# bridge.net
KiCad netlist of a schematic drawn in Altium Designer
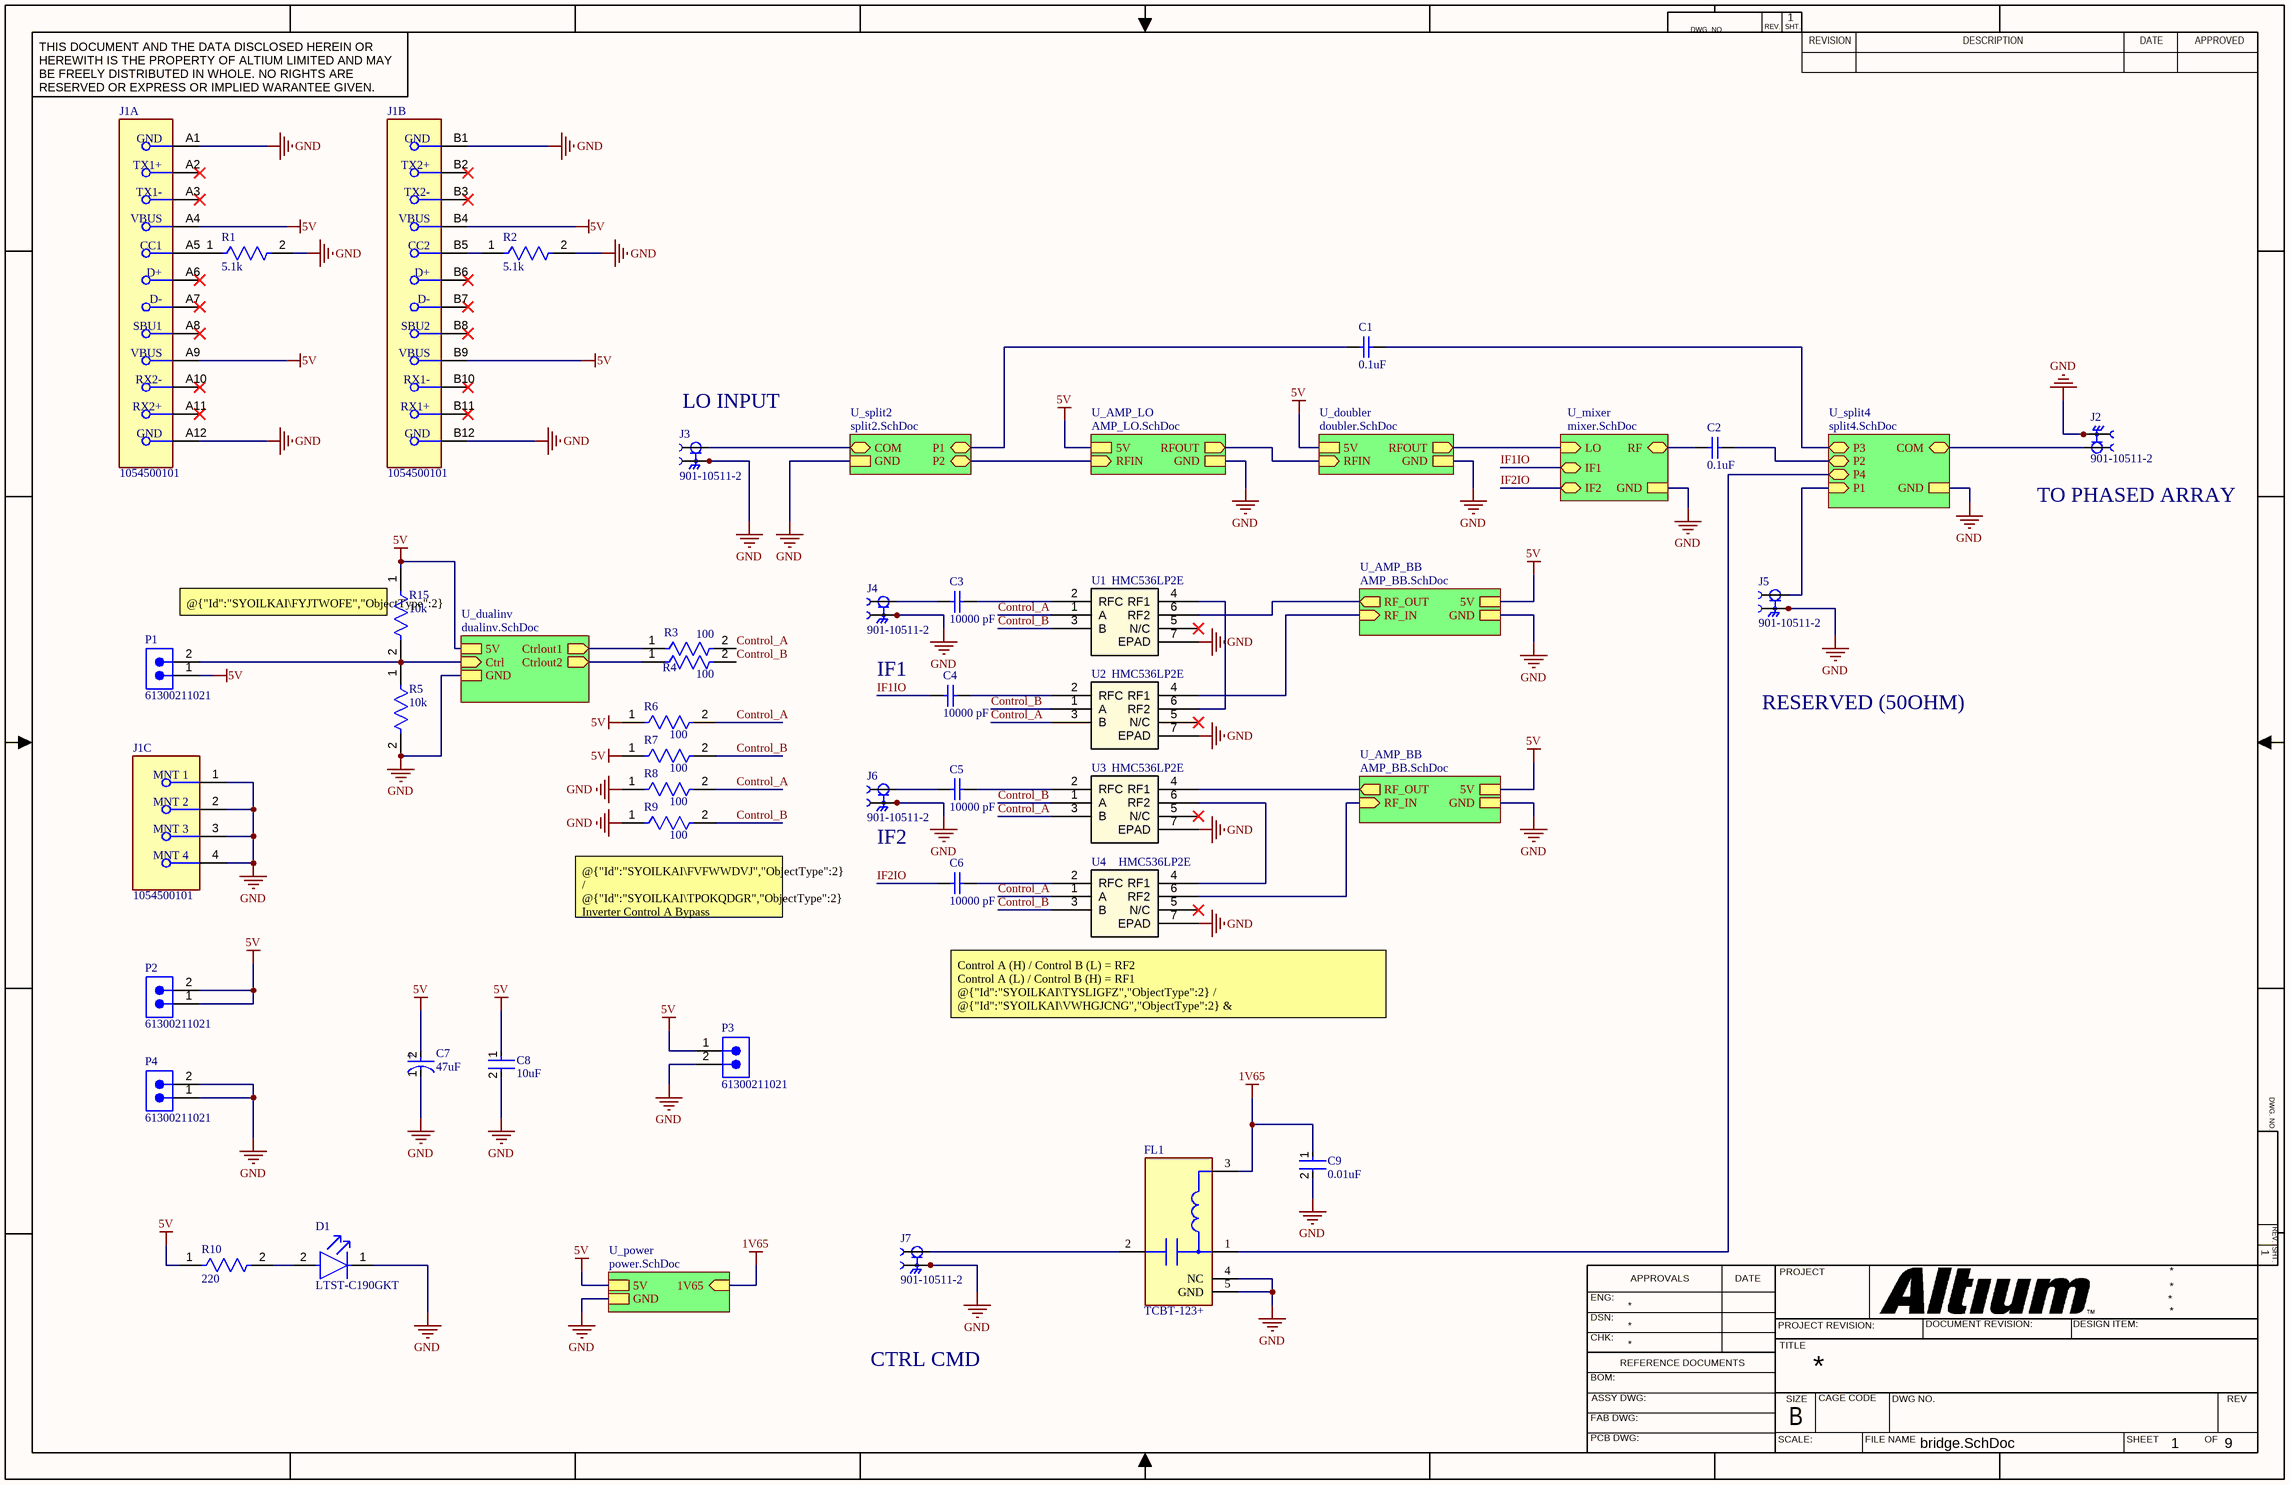
[diagram p0: bridge.SchDoc]

(export (version "E")
  (design (tool "Eeschema 10.0.6"))
  (components
    (comp (ref "C1")
      (value "0.1uF")
      (footprint "CAPC0603X33X15LL03T05")
      (description "CAP CER 0.1UF 16V X5R 0201, Broadband\r\nMultilayer Capacitor")
      (fields (field (name "MANUFACTURER") "KYOCERA AVX") (field (name "PART NUMBER") "531Z104KT16T"))
      (libsource (lib "FullLib") (part "CMP-2010-00245-1"))
    )
    (comp (ref "C2")
      (value "0.1uF")
      (footprint "CAPC0603X33X15LL03T05")
      (description "CAP CER 0.1UF 16V X5R 0201, Broadband\r\nMultilayer Capacitor")
      (fields (field (name "MANUFACTURER") "KYOCERA AVX") (field (name "PART NUMBER") "531Z104KT16T"))
      (libsource (lib "FullLib") (part "CMP-2010-00245-1"))
    )
    (comp (ref "C3")
      (value "10000 pF")
      (footprint "CAPC1005X55X25ML05T10")
      (description "CAP CER 10000PF 16V X7R 0402, RF Series")
      (fields (field (name "MANUFACTURER") "KYOCERA AVX") (field (name "PART NUMBER") "520L103KT16T"))
      (libsource (lib "FullLib") (part "CNP-CAP-10000PF-RF"))
    )
    (comp (ref "C4")
      (value "10000 pF")
      (footprint "CAPC1005X55X25ML05T10")
      (description "CAP CER 10000PF 16V X7R 0402, RF Series")
      (fields (field (name "MANUFACTURER") "KYOCERA AVX") (field (name "PART NUMBER") "520L103KT16T"))
      (libsource (lib "FullLib") (part "CNP-CAP-10000PF-RF"))
    )
    (comp (ref "C5")
      (value "10000 pF")
      (footprint "CAPC1005X55X25ML05T10")
      (description "CAP CER 10000PF 16V X7R 0402, RF Series")
      (fields (field (name "MANUFACTURER") "KYOCERA AVX") (field (name "PART NUMBER") "520L103KT16T"))
      (libsource (lib "FullLib") (part "CNP-CAP-10000PF-RF"))
    )
    (comp (ref "C6")
      (value "10000 pF")
      (footprint "CAPC1005X55X25ML05T10")
      (description "CAP CER 10000PF 16V X7R 0402, RF Series")
      (fields (field (name "MANUFACTURER") "KYOCERA AVX") (field (name "PART NUMBER") "520L103KT16T"))
      (libsource (lib "FullLib") (part "CNP-CAP-10000PF-RF"))
    )
    (comp (ref "C7")
      (value "47uF")
      (footprint "FP-TAJB-MFG")
      (description "47uF 10V  ±10% 1Ω 1210  SMD Tantalum Capacitor")
      (fields (field (name "VOLTAGE") "10V") (field (name "TOLERANCE") "10%"))
      (libsource (lib "FullLib") (part "CMP-04424-000629-1"))
    )
    (comp (ref "C8")
      (value "10uF")
      (footprint "FP-ZRB18AR61E106ME01L-MFG")
      (description "CAP CER 10UF 25V X5R 0603")
      (fields (field (name "VOLTAGE") "25V") (field (name "TOLERANCE") "20%"))
      (libsource (lib "FullLib") (part "CMP-06035-062385-2"))
    )
    (comp (ref "C9")
      (value "0.01uF")
      (footprint "FP-C0402-BB-MFG")
      (description "CAP CER 10000PF 50V X7R 0402")
      (fields (field (name "TOLERANCE") "0.1") (field (name "MANUFACTURER") "Murata"))
      (libsource (lib "FullLib") (part "CMP-2008-02109-2"))
    )
    (comp (ref "D1")
      (value "LTST-C190GKT")
      (footprint "FP-LTST-C190GKT-MFG")
      (description "LED GREEN CLEAR CHIP SMD")
      (fields (field (name "VOLTAGE") "2V") (field (name "MANUFACTURER") "Lite-On"))
      (libsource (lib "FullLib") (part "CMP-22017-000005-2"))
    )
    (comp (ref "FL1")
      (value "TCBT-123+")
      (footprint "FP-GU1414-MFG")
      (description "TCBT-123+ OEMs, CMs ONLY (NO BROKERS),  \r\nBIAS TEE SMT, 10 MHZ - 12 GHZ, 5")
      (fields (field (name "MANUFACTURER") "Mini-Circuits"))
      (libsource (lib "FullLib") (part "CMP-01968-107855816-1"))
    )
    (comp (ref "J1")
      (value "1054500101")
      (footprint "FP-1054500101-MFG")
      (description "CONN RCP USB3.1 TYPEC 24P SMD RA")
      (fields (field (name "MANUFACTURER") "Molex"))
      (libsource (lib "FullLib") (part "CMP-04767-000004-1"))
    )
    (comp (ref "J2")
      (value "901-10511-2")
      (footprint "AMPHENOL_901-10511-2")
      (fields (field (name "MANUFACTURER") "Amphenol RF"))
      (libsource (lib "Connectors") (part "901-10511-2"))
    )
    (comp (ref "J3")
      (value "901-10511-2")
      (footprint "AMPHENOL_901-10511-2")
      (fields (field (name "MANUFACTURER") "Amphenol RF"))
      (libsource (lib "Connectors") (part "901-10511-2"))
    )
    (comp (ref "J4")
      (value "901-10511-2")
      (footprint "AMPHENOL_901-10511-2")
      (fields (field (name "MANUFACTURER") "Amphenol RF"))
      (libsource (lib "Connectors") (part "901-10511-2"))
    )
    (comp (ref "J5")
      (value "901-10511-2")
      (footprint "AMPHENOL_901-10511-2")
      (fields (field (name "MANUFACTURER") "Amphenol RF"))
      (libsource (lib "Connectors") (part "901-10511-2"))
    )
    (comp (ref "J6")
      (value "901-10511-2")
      (footprint "AMPHENOL_901-10511-2")
      (fields (field (name "MANUFACTURER") "Amphenol RF"))
      (libsource (lib "Connectors") (part "901-10511-2"))
    )
    (comp (ref "J7")
      (value "901-10511-2")
      (footprint "AMPHENOL_901-10511-2")
      (fields (field (name "MANUFACTURER") "Amphenol RF"))
      (libsource (lib "Connectors") (part "901-10511-2"))
    )
    (comp (ref "P1")
      (value "61300211021")
      (footprint "61300211021")
      (description "CONN HEADER R/A 2POS 2.54MM")
      (fields (field (name "MANUFACTURER") "Wurth"))
      (libsource (lib "FullLib") (part "CMP-1502-01059-3"))
    )
    (comp (ref "P2")
      (value "61300211021")
      (footprint "61300211021")
      (description "CONN HEADER R/A 2POS 2.54MM")
      (fields (field (name "MANUFACTURER") "Wurth"))
      (libsource (lib "FullLib") (part "CMP-1502-01059-3"))
    )
    (comp (ref "P3")
      (value "61300211021")
      (footprint "61300211021")
      (description "CONN HEADER R/A 2POS 2.54MM")
      (fields (field (name "MANUFACTURER") "Wurth"))
      (libsource (lib "FullLib") (part "CMP-1502-01059-3"))
    )
    (comp (ref "P4")
      (value "61300211021")
      (footprint "61300211021")
      (description "CONN HEADER R/A 2POS 2.54MM")
      (fields (field (name "MANUFACTURER") "Wurth"))
      (libsource (lib "FullLib") (part "CMP-1502-01059-3"))
    )
    (comp (ref "R1")
      (value "5.1k")
      (footprint "FP-CRCW0603-e3-IPC_C")
      (description "RES Thick Film, 5.1kΩ, 1%, 0.1W, 100ppm/°C, 0603")
      (fields (field (name "TOLERANCE") "1%") (field (name "PART NUMBER") "ERJ-3EKF5101V"))
      (libsource (lib "FullLib") (part "CMP-1012-00590-3"))
    )
    (comp (ref "R2")
      (value "5.1k")
      (footprint "FP-CRCW0603-e3-IPC_C")
      (description "RES Thick Film, 5.1kΩ, 1%, 0.1W, 100ppm/°C, 0603")
      (fields (field (name "TOLERANCE") "1%") (field (name "PART NUMBER") "ERJ-3EKF5101V"))
      (libsource (lib "FullLib") (part "CMP-1012-00590-3"))
    )
    (comp (ref "R3")
      (value "100")
      (footprint "FP-RC0603-0_55-MFG")
      (description "RES SMD 100 OHM 5% 1/10W 0603")
      (fields (field (name "TOLERANCE") "5%") (field (name "MANUFACTURER") "Panasonic"))
      (libsource (lib "FullLib") (part "CMP-2000-05021-2"))
    )
    (comp (ref "R4")
      (value "100")
      (footprint "FP-RC0603-0_55-MFG")
      (description "RES SMD 100 OHM 5% 1/10W 0603")
      (fields (field (name "TOLERANCE") "5%") (field (name "MANUFACTURER") "Panasonic"))
      (libsource (lib "FullLib") (part "CMP-2000-05021-2"))
    )
    (comp (ref "R5")
      (value "10k")
      (footprint "FP-RC0603-0_55-IPC_C")
      (description "RES 10K OHM 1% 1/10W 0603")
      (fields (field (name "TOLERANCE") "1%") (field (name "PART NUMBER") "ERJ-S03F1002V"))
      (libsource (lib "FullLib") (part "CMP-2100-03664-2"))
    )
    (comp (ref "R6")
      (value "100")
      (footprint "FP-RC0603-0_55-MFG")
      (description "RES SMD 100 OHM 5% 1/10W 0603")
      (fields (field (name "TOLERANCE") "5%") (field (name "MANUFACTURER") "Panasonic"))
      (libsource (lib "FullLib") (part "CMP-2000-05021-2"))
    )
    (comp (ref "R7")
      (value "100")
      (footprint "FP-RC0603-0_55-MFG")
      (description "RES SMD 100 OHM 5% 1/10W 0603")
      (fields (field (name "TOLERANCE") "5%") (field (name "MANUFACTURER") "Panasonic"))
      (libsource (lib "FullLib") (part "CMP-2000-05021-2"))
    )
    (comp (ref "R8")
      (value "100")
      (footprint "FP-RC0603-0_55-MFG")
      (description "RES SMD 100 OHM 5% 1/10W 0603")
      (fields (field (name "TOLERANCE") "5%") (field (name "MANUFACTURER") "Panasonic"))
      (libsource (lib "FullLib") (part "CMP-2000-05021-2"))
    )
    (comp (ref "R9")
      (value "100")
      (footprint "FP-RC0603-0_55-MFG")
      (description "RES SMD 100 OHM 5% 1/10W 0603")
      (fields (field (name "TOLERANCE") "5%") (field (name "MANUFACTURER") "Panasonic"))
      (libsource (lib "FullLib") (part "CMP-2000-05021-2"))
    )
    (comp (ref "R10")
      (value "220")
      (footprint "FP-ERJ3G-MFG")
      (description "RES SMD 220 OHM 5% 1/10W 0603")
      (fields (field (name "TOLERANCE") "5%") (field (name "MANUFACTURER") "Panasonic"))
      (libsource (lib "FullLib") (part "CMP-2000-00746-2"))
    )
    (comp (ref "R15")
      (value "10k")
      (footprint "FP-RC0603-0_55-IPC_C")
      (description "RES 10K OHM 1% 1/10W 0603")
      (fields (field (name "TOLERANCE") "1%") (field (name "PART NUMBER") "ERJ-S03F1002V"))
      (libsource (lib "FullLib") (part "CMP-2100-03664-2"))
    )
    (comp (ref "U1")
      (value "HMC536LP2E")
      (footprint "HMC536LP2E")
      (description "IC RF SWITCH SPDT 6GHZ 6DFN")
      (fields (field (name "MANUFACTURER") "Analog Devices"))
      (libsource (lib "FullyDigital") (part "HMC536LP2E"))
    )
    (comp (ref "U2")
      (value "HMC536LP2E")
      (footprint "HMC536LP2E")
      (description "IC RF SWITCH SPDT 6GHZ 6DFN")
      (fields (field (name "MANUFACTURER") "Analog Devices"))
      (libsource (lib "FullyDigital") (part "HMC536LP2E"))
    )
    (comp (ref "U3")
      (value "HMC536LP2E")
      (footprint "HMC536LP2E")
      (description "IC RF SWITCH SPDT 6GHZ 6DFN")
      (fields (field (name "MANUFACTURER") "Analog Devices"))
      (libsource (lib "FullyDigital") (part "HMC536LP2E"))
    )
    (comp (ref "U4")
      (value "HMC536LP2E")
      (footprint "HMC536LP2E")
      (description "IC RF SWITCH SPDT 6GHZ 6DFN")
      (fields (field (name "MANUFACTURER") "Analog Devices"))
      (libsource (lib "FullyDigital") (part "HMC536LP2E"))
    )
  )
  (nets
    (net (code "1") (name "/COM") (class "Default")
      (node (ref "J2") (pin "1") (pinfunction "1_1") (pintype "passive"))
    )
    (net (code "2") (name "/COM_1") (class "Default")
      (node (ref "J3") (pin "1") (pinfunction "1_1") (pintype "passive"))
    )
    (net (code "3") (name "/Control_A") (class "Default")
      (node (ref "R3") (pin "2") (pinfunction "2_2") (pintype "passive"))
      (node (ref "R6") (pin "2") (pinfunction "2_2") (pintype "passive"))
      (node (ref "R8") (pin "2") (pinfunction "2_2") (pintype "passive"))
      (node (ref "U1") (pin "1") (pinfunction "A_1") (pintype "passive"))
      (node (ref "U2") (pin "3") (pinfunction "B_3") (pintype "passive"))
      (node (ref "U3") (pin "3") (pinfunction "B_3") (pintype "passive"))
      (node (ref "U4") (pin "1") (pinfunction "A_1") (pintype "passive"))
    )
    (net (code "4") (name "/Control_B") (class "Default")
      (node (ref "R4") (pin "2") (pinfunction "2_2") (pintype "passive"))
      (node (ref "R7") (pin "2") (pinfunction "2_2") (pintype "passive"))
      (node (ref "R9") (pin "2") (pinfunction "2_2") (pintype "passive"))
      (node (ref "U1") (pin "3") (pinfunction "B_3") (pintype "passive"))
      (node (ref "U2") (pin "1") (pinfunction "A_1") (pintype "passive"))
      (node (ref "U3") (pin "1") (pinfunction "A_1") (pintype "passive"))
      (node (ref "U4") (pin "3") (pinfunction "B_3") (pintype "passive"))
    )
    (net (code "5") (name "/Ctrl") (class "Default")
      (node (ref "P1") (pin "2") (pinfunction "2_2") (pintype "passive"))
      (node (ref "R15") (pin "2") (pinfunction "2_2") (pintype "passive"))
      (node (ref "R5") (pin "1") (pinfunction "1_1") (pintype "passive"))
    )
    (net (code "6") (name "/Ctrlout1") (class "Default")
      (node (ref "R3") (pin "1") (pinfunction "1_1") (pintype "passive"))
    )
    (net (code "7") (name "/Ctrlout2") (class "Default")
      (node (ref "R4") (pin "1") (pinfunction "1_1") (pintype "passive"))
    )
    (net (code "8") (name "/IF1IO") (class "Default")
      (node (ref "C4") (pin "1") (pinfunction "1_1") (pintype "passive"))
    )
    (net (code "9") (name "/IF2IO") (class "Default")
      (node (ref "C6") (pin "1") (pinfunction "1_1") (pintype "passive"))
    )
    (net (code "10") (name "/P1") (class "Default")
      (node (ref "J5") (pin "1") (pinfunction "1_1") (pintype "passive"))
    )
    (net (code "11") (name "/P1_1") (class "Default")
      (node (ref "C1") (pin "1") (pinfunction "1_1") (pintype "passive"))
    )
    (net (code "13") (name "/P2_1") (class "Default")
      (node (ref "C2") (pin "2") (pinfunction "2_2") (pintype "passive"))
    )
    (net (code "14") (name "/P3") (class "Default")
      (node (ref "C1") (pin "2") (pinfunction "2_2") (pintype "passive"))
    )
    (net (code "15") (name "/P4") (class "Default")
      (node (ref "FL1") (pin "1") (pinfunction "RF&DC_1") (pintype "passive"))
    )
    (net (code "16") (name "/RF") (class "Default")
      (node (ref "C2") (pin "1") (pinfunction "1_1") (pintype "passive"))
    )
    (net (code "19") (name "/RF_IN") (class "Default")
      (node (ref "U2") (pin "4") (pinfunction "RF1_4") (pintype "passive"))
    )
    (net (code "20") (name "/RF_IN_1") (class "Default")
      (node (ref "U4") (pin "6") (pinfunction "RF2_6") (pintype "passive"))
    )
    (net (code "21") (name "/RF_OUT") (class "Default")
      (node (ref "U3") (pin "4") (pinfunction "RF1_4") (pintype "passive"))
    )
    (net (code "22") (name "/RF_OUT_1") (class "Default")
      (node (ref "U1") (pin "6") (pinfunction "RF2_6") (pintype "passive"))
    )
    (net (code "23") (name "1V65") (class "Default")
      (node (ref "C9") (pin "1") (pinfunction "1_1") (pintype "passive"))
      (node (ref "FL1") (pin "3") (pinfunction "DC_3") (pintype "passive"))
    )
    (net (code "24") (name "5V") (class "Default")
      (node (ref "C7") (pin "2") (pinfunction "A_2") (pintype "passive"))
      (node (ref "C8") (pin "1") (pinfunction "1_1") (pintype "passive"))
      (node (ref "J1") (pin "A4") (pinfunction "VBUS_A4") (pintype "passive"))
      (node (ref "J1") (pin "A9") (pinfunction "VBUS_A9") (pintype "passive"))
      (node (ref "J1") (pin "B4") (pinfunction "VBUS_B4") (pintype "passive"))
      (node (ref "J1") (pin "B9") (pinfunction "VBUS_B9") (pintype "passive"))
      (node (ref "P1") (pin "1") (pinfunction "1_1") (pintype "passive"))
      (node (ref "P2") (pin "1") (pinfunction "1_1") (pintype "passive"))
      (node (ref "P2") (pin "2") (pinfunction "2_2") (pintype "passive"))
      (node (ref "P3") (pin "1") (pinfunction "1_1") (pintype "passive"))
      (node (ref "R10") (pin "1") (pinfunction "1_1") (pintype "passive"))
      (node (ref "R15") (pin "1") (pinfunction "1_1") (pintype "passive"))
      (node (ref "R6") (pin "1") (pinfunction "1_1") (pintype "passive"))
      (node (ref "R7") (pin "1") (pinfunction "1_1") (pintype "passive"))
    )
    (net (code "25") (name "GND") (class "Default")
      (node (ref "C7") (pin "1") (pinfunction "C_1") (pintype "passive"))
      (node (ref "C8") (pin "2") (pinfunction "2_2") (pintype "passive"))
      (node (ref "C9") (pin "2") (pinfunction "2_2") (pintype "passive"))
      (node (ref "D1") (pin "1") (pinfunction "C_1") (pintype "passive"))
      (node (ref "FL1") (pin "4") (pinfunction "NC_4") (pintype "passive"))
      (node (ref "FL1") (pin "5") (pinfunction "GND_5") (pintype "power_in"))
      (node (ref "J1") (pin "1") (pinfunction "MNT_1_1") (pintype "passive"))
      (node (ref "J1") (pin "2") (pinfunction "MNT_2_2") (pintype "passive"))
      (node (ref "J1") (pin "3") (pinfunction "MNT_3_3") (pintype "passive"))
      (node (ref "J1") (pin "4") (pinfunction "MNT_4_4") (pintype "passive"))
      (node (ref "J1") (pin "A1") (pinfunction "GND_A1") (pintype "passive"))
      (node (ref "J1") (pin "A12") (pinfunction "GND_A12") (pintype "passive"))
      (node (ref "J1") (pin "B1") (pinfunction "GND_B1") (pintype "passive"))
      (node (ref "J1") (pin "B12") (pinfunction "GND_B12") (pintype "passive"))
      (node (ref "J2") (pin "G1") (pinfunction "2_G1") (pintype "passive"))
      (node (ref "J2") (pin "G2") (pinfunction "2_G2") (pintype "passive"))
      (node (ref "J3") (pin "G1") (pinfunction "2_G1") (pintype "passive"))
      (node (ref "J3") (pin "G2") (pinfunction "2_G2") (pintype "passive"))
      (node (ref "J4") (pin "G1") (pinfunction "2_G1") (pintype "passive"))
      (node (ref "J4") (pin "G2") (pinfunction "2_G2") (pintype "passive"))
      (node (ref "J5") (pin "G1") (pinfunction "2_G1") (pintype "passive"))
      (node (ref "J5") (pin "G2") (pinfunction "2_G2") (pintype "passive"))
      (node (ref "J6") (pin "G1") (pinfunction "2_G1") (pintype "passive"))
      (node (ref "J6") (pin "G2") (pinfunction "2_G2") (pintype "passive"))
      (node (ref "J7") (pin "G1") (pinfunction "2_G1") (pintype "passive"))
      (node (ref "J7") (pin "G2") (pinfunction "2_G2") (pintype "passive"))
      (node (ref "P3") (pin "2") (pinfunction "2_2") (pintype "passive"))
      (node (ref "P4") (pin "1") (pinfunction "1_1") (pintype "passive"))
      (node (ref "P4") (pin "2") (pinfunction "2_2") (pintype "passive"))
      (node (ref "R1") (pin "2") (pinfunction "2_2") (pintype "passive"))
      (node (ref "R2") (pin "2") (pinfunction "2_2") (pintype "passive"))
      (node (ref "R5") (pin "2") (pinfunction "2_2") (pintype "passive"))
      (node (ref "R8") (pin "1") (pinfunction "1_1") (pintype "passive"))
      (node (ref "R9") (pin "1") (pinfunction "1_1") (pintype "passive"))
      (node (ref "U1") (pin "7") (pinfunction "EPAD_7") (pintype "passive"))
      (node (ref "U2") (pin "7") (pinfunction "EPAD_7") (pintype "passive"))
      (node (ref "U3") (pin "7") (pinfunction "EPAD_7") (pintype "passive"))
      (node (ref "U4") (pin "7") (pinfunction "EPAD_7") (pintype "passive"))
    )
    (net (code "26") (name "Net-(C3-Pad1)") (class "Default")
      (node (ref "C3") (pin "1") (pinfunction "1_1") (pintype "passive"))
      (node (ref "J4") (pin "1") (pinfunction "1_1") (pintype "passive"))
    )
    (net (code "27") (name "Net-(C5-Pad1)") (class "Default")
      (node (ref "C5") (pin "1") (pinfunction "1_1") (pintype "passive"))
      (node (ref "J6") (pin "1") (pinfunction "1_1") (pintype "passive"))
    )
    (net (code "28") (name "Net-(D1-A)") (class "Default")
      (node (ref "D1") (pin "2") (pinfunction "A_2") (pintype "passive"))
      (node (ref "R10") (pin "2") (pinfunction "2_2") (pintype "passive"))
    )
    (net (code "29") (name "Net-(FL1-RF)") (class "Default")
      (node (ref "FL1") (pin "2") (pinfunction "RF_2") (pintype "passive"))
      (node (ref "J7") (pin "1") (pinfunction "1_1") (pintype "passive"))
    )
    (net (code "30") (name "Net-(J1A-CC1)") (class "Default")
      (node (ref "J1") (pin "A5") (pinfunction "CC1_A5") (pintype "passive"))
      (node (ref "R1") (pin "1") (pinfunction "1_1") (pintype "passive"))
    )
    (net (code "31") (name "Net-(J1B-CC2)") (class "Default")
      (node (ref "J1") (pin "B5") (pinfunction "CC2_B5") (pintype "passive"))
      (node (ref "R2") (pin "1") (pinfunction "1_1") (pintype "passive"))
    )
    (net (code "32") (name "Net-(U1-RF1)") (class "Default")
      (node (ref "U1") (pin "4") (pinfunction "RF1_4") (pintype "passive"))
      (node (ref "U2") (pin "6") (pinfunction "RF2_6") (pintype "passive"))
    )
    (net (code "33") (name "Net-(U1-RFC)") (class "Default")
      (node (ref "C3") (pin "2") (pinfunction "2_2") (pintype "passive"))
      (node (ref "U1") (pin "2") (pinfunction "RFC_2") (pintype "passive"))
    )
    (net (code "34") (name "Net-(U2-RFC)") (class "Default")
      (node (ref "C4") (pin "2") (pinfunction "2_2") (pintype "passive"))
      (node (ref "U2") (pin "2") (pinfunction "RFC_2") (pintype "passive"))
    )
    (net (code "35") (name "Net-(U3-RF2)") (class "Default")
      (node (ref "U3") (pin "6") (pinfunction "RF2_6") (pintype "passive"))
      (node (ref "U4") (pin "4") (pinfunction "RF1_4") (pintype "passive"))
    )
    (net (code "36") (name "Net-(U3-RFC)") (class "Default")
      (node (ref "C5") (pin "2") (pinfunction "2_2") (pintype "passive"))
      (node (ref "U3") (pin "2") (pinfunction "RFC_2") (pintype "passive"))
    )
    (net (code "37") (name "Net-(U4-RFC)") (class "Default")
      (node (ref "C6") (pin "2") (pinfunction "2_2") (pintype "passive"))
      (node (ref "U4") (pin "2") (pinfunction "RFC_2") (pintype "passive"))
    )
    (net (code "38") (name "unconnected-(J1A-D+-PadA6)") (class "Default")
      (node (ref "J1") (pin "A6") (pinfunction "D+_A6") (pintype "passive+no_connect"))
    )
    (net (code "39") (name "unconnected-(J1A-D--PadA7)") (class "Default")
      (node (ref "J1") (pin "A7") (pinfunction "D-_A7") (pintype "passive+no_connect"))
    )
    (net (code "40") (name "unconnected-(J1A-RX2+-PadA11)") (class "Default")
      (node (ref "J1") (pin "A11") (pinfunction "RX2+_A11") (pintype "passive+no_connect"))
    )
    (net (code "41") (name "unconnected-(J1A-RX2--PadA10)") (class "Default")
      (node (ref "J1") (pin "A10") (pinfunction "RX2-_A10") (pintype "passive+no_connect"))
    )
    (net (code "42") (name "unconnected-(J1A-SBU1-PadA8)") (class "Default")
      (node (ref "J1") (pin "A8") (pinfunction "SBU1_A8") (pintype "passive+no_connect"))
    )
    (net (code "43") (name "unconnected-(J1A-TX1+-PadA2)") (class "Default")
      (node (ref "J1") (pin "A2") (pinfunction "TX1+_A2") (pintype "passive+no_connect"))
    )
    (net (code "44") (name "unconnected-(J1A-TX1--PadA3)") (class "Default")
      (node (ref "J1") (pin "A3") (pinfunction "TX1-_A3") (pintype "passive+no_connect"))
    )
    (net (code "45") (name "unconnected-(J1B-D+-PadB6)") (class "Default")
      (node (ref "J1") (pin "B6") (pinfunction "D+_B6") (pintype "passive+no_connect"))
    )
    (net (code "46") (name "unconnected-(J1B-D--PadB7)") (class "Default")
      (node (ref "J1") (pin "B7") (pinfunction "D-_B7") (pintype "passive+no_connect"))
    )
    (net (code "47") (name "unconnected-(J1B-RX1+-PadB11)") (class "Default")
      (node (ref "J1") (pin "B11") (pinfunction "RX1+_B11") (pintype "passive+no_connect"))
    )
    (net (code "48") (name "unconnected-(J1B-RX1--PadB10)") (class "Default")
      (node (ref "J1") (pin "B10") (pinfunction "RX1-_B10") (pintype "passive+no_connect"))
    )
    (net (code "49") (name "unconnected-(J1B-SBU2-PadB8)") (class "Default")
      (node (ref "J1") (pin "B8") (pinfunction "SBU2_B8") (pintype "passive+no_connect"))
    )
    (net (code "50") (name "unconnected-(J1B-TX2+-PadB2)") (class "Default")
      (node (ref "J1") (pin "B2") (pinfunction "TX2+_B2") (pintype "passive+no_connect"))
    )
    (net (code "51") (name "unconnected-(J1B-TX2--PadB3)") (class "Default")
      (node (ref "J1") (pin "B3") (pinfunction "TX2-_B3") (pintype "passive+no_connect"))
    )
    (net (code "52") (name "unconnected-(U1-N{slash}C-Pad5)") (class "Default")
      (node (ref "U1") (pin "5") (pinfunction "N/C_5") (pintype "passive+no_connect"))
    )
    (net (code "53") (name "unconnected-(U2-N{slash}C-Pad5)") (class "Default")
      (node (ref "U2") (pin "5") (pinfunction "N/C_5") (pintype "passive+no_connect"))
    )
    (net (code "54") (name "unconnected-(U3-N{slash}C-Pad5)") (class "Default")
      (node (ref "U3") (pin "5") (pinfunction "N/C_5") (pintype "passive+no_connect"))
    )
    (net (code "55") (name "unconnected-(U4-N{slash}C-Pad5)") (class "Default")
      (node (ref "U4") (pin "5") (pinfunction "N/C_5") (pintype "passive+no_connect"))
    )
  )
)
